# ARM.net
KiCad netlist of a schematic drawn in Altium Designer
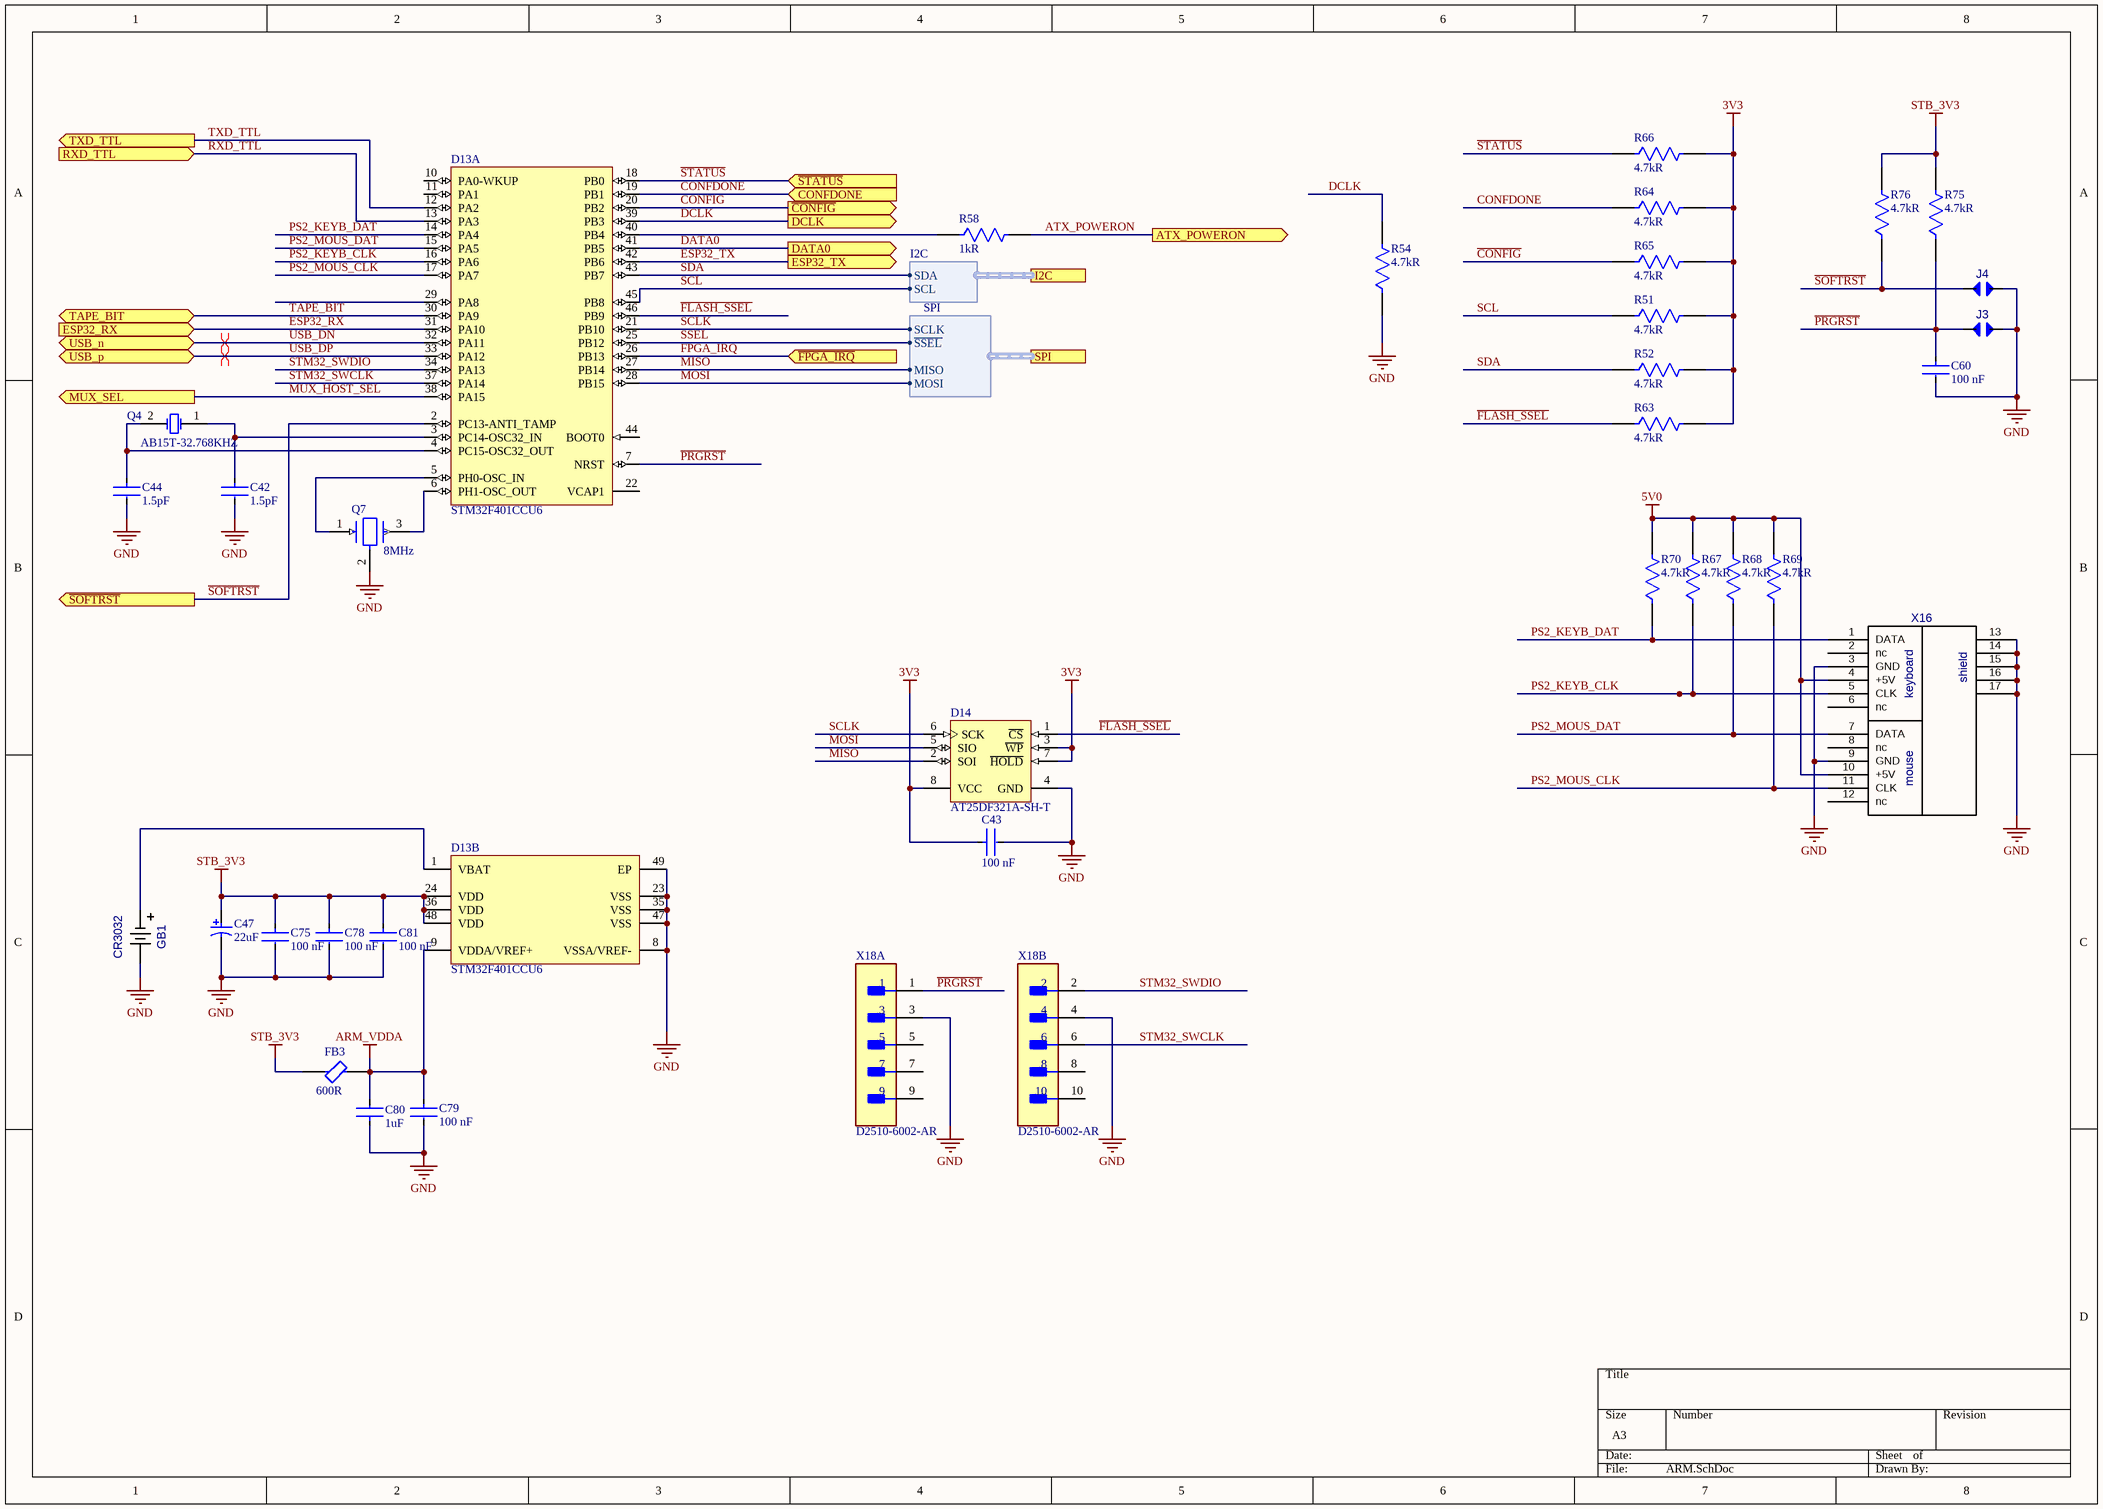
[diagram p0: ARM.SchDoc]

(export (version "E")
  (design (tool "Eeschema 10.0.6"))
  (components
    (comp (ref "C42")
      (value "CL21C1R5CBANNNC")
      (footprint "FP-CL21-IPC_A")
      (description "CL21 Series 0805 1.5pF 50V ±0.25pF Tolerance C0G Multilayer Ceramic Chip Capacitor")
      (fields (field (name "VOLTAGE") "50V") (field (name "CAPACITANCE") "1.5pF"))
      (libsource (lib "Altium Content Vault") (part "b4654b650e69147ec39a6b967a45e02"))
    )
    (comp (ref "C43")
      (value "CC0805KRX7R8BB104")
      (footprint "FP-CC0805-0_85-IPC_A")
      (description "CAP CER 0.1UF 25V X7R 0805")
      (fields
        (field (name "TOLERANCE") "0.1")
        (field (name "MANUFACTURER") "Yageo")
        (field (name "CAPACITANCE") "100 nF")
      )
      (libsource (lib "Altium Content Vault") (part "11868f565c42a9108669ba33697ecf6"))
    )
    (comp (ref "C44")
      (value "CL21C1R5CBANNNC")
      (footprint "FP-CL21-IPC_A")
      (description "CL21 Series 0805 1.5pF 50V ±0.25pF Tolerance C0G Multilayer Ceramic Chip Capacitor")
      (fields (field (name "VOLTAGE") "50V") (field (name "CAPACITANCE") "1.5pF"))
      (libsource (lib "Altium Content Vault") (part "b4654b650e69147ec39a6b967a45e02"))
    )
    (comp (ref "C47")
      (value "TAJB226K016RNJ")
      (footprint "AVX-TAJ-B-2_M")
      (description "Standard Tantalum, 22 uF, +/- 10%, 16 V, -55 to 125 degC, 2-Pin SMD (1210), RoHS, Tape and Reel")
      (fields
        (field (name "TOLERANCE") "10%")
        (field (name "CAPACITANCE") "22uF")
        (field (name "MANUFACTURER") "AVX")
      )
      (libsource (lib "Altium Content Vault") (part "CAP-P-2"))
    )
    (comp (ref "C60")
      (value "CC0805KRX7R8BB104")
      (footprint "FP-CC0805-0_85-IPC_A")
      (description "CAP CER 0.1UF 25V X7R 0805")
      (fields
        (field (name "TOLERANCE") "0.1")
        (field (name "MANUFACTURER") "Yageo")
        (field (name "CAPACITANCE") "100 nF")
      )
      (libsource (lib "Altium Content Vault") (part "11868f565c42a9108669ba33697ecf6"))
    )
    (comp (ref "C75")
      (value "CC0805KRX7R8BB104")
      (footprint "FP-CC0805-0_85-IPC_A")
      (description "CAP CER 0.1UF 25V X7R 0805")
      (fields
        (field (name "TOLERANCE") "0.1")
        (field (name "MANUFACTURER") "Yageo")
        (field (name "CAPACITANCE") "100 nF")
      )
      (libsource (lib "Altium Content Vault") (part "11868f565c42a9108669ba33697ecf6"))
    )
    (comp (ref "C78")
      (value "CC0805KRX7R8BB104")
      (footprint "FP-CC0805-0_85-IPC_A")
      (description "CAP CER 0.1UF 25V X7R 0805")
      (fields
        (field (name "TOLERANCE") "0.1")
        (field (name "MANUFACTURER") "Yageo")
        (field (name "CAPACITANCE") "100 nF")
      )
      (libsource (lib "Altium Content Vault") (part "11868f565c42a9108669ba33697ecf6"))
    )
    (comp (ref "C79")
      (value "CC0805KRX7R8BB104")
      (footprint "FP-CC0805-0_85-IPC_A")
      (description "CAP CER 0.1UF 25V X7R 0805")
      (fields
        (field (name "TOLERANCE") "0.1")
        (field (name "MANUFACTURER") "Yageo")
        (field (name "CAPACITANCE") "100 nF")
      )
      (libsource (lib "Altium Content Vault") (part "11868f565c42a9108669ba33697ecf6"))
    )
    (comp (ref "C80")
      (value "GCM21BR71E105KA56L")
      (footprint "FP-GCM21B-0_15-IPC_A")
      (description "Ceramic Capacitor for Automotive 1uF ±10% 25VDC X7R 0805 Embossed T/R")
      (fields
        (field (name "TOLERANCE") "10%")
        (field (name "VOLTAGE") "25V")
        (field (name "CAPACITANCE") "1uF")
      )
      (libsource (lib "Altium Content Vault") (part "02cd4be3c70576c341d710602a673aa"))
    )
    (comp (ref "C81")
      (value "CC0805KRX7R8BB104")
      (footprint "FP-CC0805-0_85-IPC_A")
      (description "CAP CER 0.1UF 25V X7R 0805")
      (fields
        (field (name "TOLERANCE") "0.1")
        (field (name "MANUFACTURER") "Yageo")
        (field (name "CAPACITANCE") "100 nF")
      )
      (libsource (lib "Altium Content Vault") (part "11868f565c42a9108669ba33697ecf6"))
    )
    (comp (ref "D13")
      (value "STM32F401CCU6")
      (footprint "STM-UFQFPN48_N")
      (fields (field (name "MANUFACTURER") "STMicroelectronics"))
      (libsource (lib "zxevo_c2") (part "CMP-0243-00119-2"))
    )
    (comp (ref "D14")
      (value "AT25DF321A-SH-T")
      (footprint "ADST-S2-8_N")
      (fields (field (name "MANUFACTURER") "Adesto"))
      (libsource (lib "Altium Content Vault") (part "ADST-AT25DF321A-8"))
    )
    (comp (ref "FB3")
      (value "BLM21AG601SN1J")
      (footprint "FP-BLM21-0_2-t0_85-e0_5-IPC_A")
      (description "Chip Ferrite Bead, 0805, 600Ω @ 100MHz, 0.2Ω, 25%, 700mA")
      (fields (field (name "IMPEDANCE") "600R") (field (name "TOLERANCE") "25%"))
      (libsource (lib "Altium Content Vault") (part "5f30dd21d616792df468990f7003faa"))
    )
    (comp (ref "GB1")
      (value "CR3032")
      (footprint "BAT_Primary")
      (description "BAT")
      (libsource (lib "*") (part "BAT"))
    )
    (comp (ref "J3")
      (value "JUMPER")
      (footprint "JUMPER")
      (description "Hard Reset Key")
      (libsource (lib "*") (part "JUMPER"))
    )
    (comp (ref "J4")
      (value "JUMPER")
      (footprint "JUMPER")
      (description "Soft Reset Key")
      (libsource (lib "*") (part "JUMPER"))
    )
    (comp (ref "Q4")
      (value "AB15T-32.768KHZ")
      (footprint "ABRA-AB15T-2_V")
      (fields (field (name "MANUFACTURER") "Abracon"))
      (libsource (lib "Altium Content Vault") (part "ABRA-XTAL_1-2-2"))
    )
    (comp (ref "Q7")
      (value "CSTNE8M00GH5C000R0")
      (footprint "FP-CSTNE8M00GH5C000R0-MFG")
      (description "CERAMIC RES 8.0000MHZ 33PF SMD")
      (fields (field (name "FREQUENCY") "8MHz"))
      (libsource (lib "Altium Content Vault") (part "7d37667f5012bb31280c8009ddd0b1c"))
    )
    (comp (ref "R51")
      (value "CR0805-JW-472ELF")
      (footprint "FP-CR0805-IPC_A")
      (description "Thick Film Chip Resistors 0805 4.7kΩ 0.125W 5% 200ppm/°C")
      (fields (field (name "TOLERANCE") "5%") (field (name "RESISTANCE") "4.7kR"))
      (libsource (lib "Altium Content Vault") (part "1029c3af85768c4190bb7ad29bc67b5"))
    )
    (comp (ref "R52")
      (value "CR0805-JW-472ELF")
      (footprint "FP-CR0805-IPC_A")
      (description "Thick Film Chip Resistors 0805 4.7kΩ 0.125W 5% 200ppm/°C")
      (fields (field (name "TOLERANCE") "5%") (field (name "RESISTANCE") "4.7kR"))
      (libsource (lib "Altium Content Vault") (part "1029c3af85768c4190bb7ad29bc67b5"))
    )
    (comp (ref "R54")
      (value "CR0805-JW-472ELF")
      (footprint "FP-CR0805-IPC_A")
      (description "Thick Film Chip Resistors 0805 4.7kΩ 0.125W 5% 200ppm/°C")
      (fields (field (name "TOLERANCE") "5%") (field (name "RESISTANCE") "4.7kR"))
      (libsource (lib "Altium Content Vault") (part "1029c3af85768c4190bb7ad29bc67b5"))
    )
    (comp (ref "R58")
      (value "MCR10ERTJ102")
      (footprint "FP-MCR10-IPC_A")
      (description "Thick Film Chip Resistor, 0805, 1kΩ, 5%, 200ppm/°C, 0.125W, 150V")
      (fields (field (name "RESISTANCE") "1kR") (field (name "TOLERANCE") "5%"))
      (libsource (lib "Altium Content Vault") (part "1029c3af85768c4190bb7ad29bc67b5"))
    )
    (comp (ref "R63")
      (value "CR0805-JW-472ELF")
      (footprint "FP-CR0805-IPC_A")
      (description "Thick Film Chip Resistors 0805 4.7kΩ 0.125W 5% 200ppm/°C")
      (fields (field (name "TOLERANCE") "5%") (field (name "RESISTANCE") "4.7kR"))
      (libsource (lib "Altium Content Vault") (part "1029c3af85768c4190bb7ad29bc67b5"))
    )
    (comp (ref "R64")
      (value "CR0805-JW-472ELF")
      (footprint "FP-CR0805-IPC_A")
      (description "Thick Film Chip Resistors 0805 4.7kΩ 0.125W 5% 200ppm/°C")
      (fields (field (name "TOLERANCE") "5%") (field (name "RESISTANCE") "4.7kR"))
      (libsource (lib "Altium Content Vault") (part "1029c3af85768c4190bb7ad29bc67b5"))
    )
    (comp (ref "R65")
      (value "CR0805-JW-472ELF")
      (footprint "FP-CR0805-IPC_A")
      (description "Thick Film Chip Resistors 0805 4.7kΩ 0.125W 5% 200ppm/°C")
      (fields (field (name "TOLERANCE") "5%") (field (name "RESISTANCE") "4.7kR"))
      (libsource (lib "Altium Content Vault") (part "1029c3af85768c4190bb7ad29bc67b5"))
    )
    (comp (ref "R66")
      (value "CR0805-JW-472ELF")
      (footprint "FP-CR0805-IPC_A")
      (description "Thick Film Chip Resistors 0805 4.7kΩ 0.125W 5% 200ppm/°C")
      (fields (field (name "TOLERANCE") "5%") (field (name "RESISTANCE") "4.7kR"))
      (libsource (lib "Altium Content Vault") (part "1029c3af85768c4190bb7ad29bc67b5"))
    )
    (comp (ref "R67")
      (value "CR0805-JW-472ELF")
      (footprint "FP-CR0805-IPC_A")
      (description "Thick Film Chip Resistors 0805 4.7kΩ 0.125W 5% 200ppm/°C")
      (fields (field (name "TOLERANCE") "5%") (field (name "RESISTANCE") "4.7kR"))
      (libsource (lib "Altium Content Vault") (part "1029c3af85768c4190bb7ad29bc67b5"))
    )
    (comp (ref "R68")
      (value "CR0805-JW-472ELF")
      (footprint "FP-CR0805-IPC_A")
      (description "Thick Film Chip Resistors 0805 4.7kΩ 0.125W 5% 200ppm/°C")
      (fields (field (name "TOLERANCE") "5%") (field (name "RESISTANCE") "4.7kR"))
      (libsource (lib "Altium Content Vault") (part "1029c3af85768c4190bb7ad29bc67b5"))
    )
    (comp (ref "R69")
      (value "CR0805-JW-472ELF")
      (footprint "FP-CR0805-IPC_A")
      (description "Thick Film Chip Resistors 0805 4.7kΩ 0.125W 5% 200ppm/°C")
      (fields (field (name "TOLERANCE") "5%") (field (name "RESISTANCE") "4.7kR"))
      (libsource (lib "Altium Content Vault") (part "1029c3af85768c4190bb7ad29bc67b5"))
    )
    (comp (ref "R70")
      (value "CR0805-JW-472ELF")
      (footprint "FP-CR0805-IPC_A")
      (description "Thick Film Chip Resistors 0805 4.7kΩ 0.125W 5% 200ppm/°C")
      (fields (field (name "TOLERANCE") "5%") (field (name "RESISTANCE") "4.7kR"))
      (libsource (lib "Altium Content Vault") (part "1029c3af85768c4190bb7ad29bc67b5"))
    )
    (comp (ref "R75")
      (value "CR0805-JW-472ELF")
      (footprint "FP-CR0805-IPC_A")
      (description "Thick Film Chip Resistors 0805 4.7kΩ 0.125W 5% 200ppm/°C")
      (fields (field (name "TOLERANCE") "5%") (field (name "RESISTANCE") "4.7kR"))
      (libsource (lib "Altium Content Vault") (part "1029c3af85768c4190bb7ad29bc67b5"))
    )
    (comp (ref "R76")
      (value "CR0805-JW-472ELF")
      (footprint "FP-CR0805-IPC_A")
      (description "Thick Film Chip Resistors 0805 4.7kΩ 0.125W 5% 200ppm/°C")
      (fields (field (name "TOLERANCE") "5%") (field (name "RESISTANCE") "4.7kR"))
      (libsource (lib "Altium Content Vault") (part "1029c3af85768c4190bb7ad29bc67b5"))
    )
    (comp (ref "X16") (value "KEYB-MOUSE") (footprint "MDD-6FR") (libsource (lib "*") (part "KEYB-MOUSE")))
    (comp (ref "X18")
      (value "D2510-6002-AR")
      (footprint "FP-D2510-6002-AR-MFG")
      (description "CONN HEADER VERT 10POS 2.54MM")
      (fields
        (field (name "MANUFACTURER") "3M")
        (field (name "OCTOPART") "https://octopart.com/d2510-6002-ar-3m-8399032")
      )
      (libsource (lib "Altium Content Vault") (part "e3d72e3fae012c5d23a5abbd4905472"))
    )
  )
  (nets
    (net (code "3") (name "/ATX_POWERON") (class "Default")
      (node (ref "R58") (pin "2") (pinfunction "2_2") (pintype "passive"))
    )
    (net (code "4") (name "/CONFDONE") (class "Default")
      (node (ref "D13") (pin "19") (pinfunction "PB1_19") (pintype "bidirectional"))
      (node (ref "R64") (pin "1") (pinfunction "1_1") (pintype "passive"))
    )
    (net (code "5") (name "/DATA0") (class "Default")
      (node (ref "D13") (pin "41") (pinfunction "PB5_41") (pintype "bidirectional"))
    )
    (net (code "6") (name "/DCLK") (class "Default")
      (node (ref "D13") (pin "39") (pinfunction "PB3_39") (pintype "bidirectional"))
      (node (ref "R54") (pin "2") (pinfunction "2_2") (pintype "passive"))
    )
    (net (code "7") (name "/ESP32_RX") (class "Default")
      (node (ref "D13") (pin "31") (pinfunction "PA10_31") (pintype "bidirectional"))
    )
    (net (code "8") (name "/ESP32_TX") (class "Default")
      (node (ref "D13") (pin "42") (pinfunction "PB6_42") (pintype "bidirectional"))
    )
    (net (code "9") (name "/MISO") (class "Default")
      (node (ref "D13") (pin "27") (pinfunction "PB14_27") (pintype "bidirectional"))
      (node (ref "D14") (pin "2") (pinfunction "SOI_2") (pintype "bidirectional"))
    )
    (net (code "10") (name "/MOSI") (class "Default")
      (node (ref "D13") (pin "28") (pinfunction "PB15_28") (pintype "bidirectional"))
      (node (ref "D14") (pin "5") (pinfunction "SIO_5") (pintype "bidirectional"))
    )
    (net (code "11") (name "/MUX_HOST_SEL") (class "Default")
      (node (ref "D13") (pin "38") (pinfunction "PA15_38") (pintype "bidirectional"))
    )
    (net (code "12") (name "/PS2_KEYB_CLK") (class "Default")
      (node (ref "D13") (pin "16") (pinfunction "PA6_16") (pintype "bidirectional"))
      (node (ref "R67") (pin "1") (pinfunction "1_1") (pintype "passive"))
      (node (ref "X16") (pin "5") (pinfunction "CLK_5") (pintype "passive"))
    )
    (net (code "13") (name "/PS2_KEYB_DAT") (class "Default")
      (node (ref "D13") (pin "14") (pinfunction "PA4_14") (pintype "bidirectional"))
      (node (ref "R70") (pin "1") (pinfunction "1_1") (pintype "passive"))
      (node (ref "X16") (pin "1") (pinfunction "DATA_1") (pintype "passive"))
    )
    (net (code "14") (name "/PS2_MOUS_CLK") (class "Default")
      (node (ref "D13") (pin "17") (pinfunction "PA7_17") (pintype "bidirectional"))
      (node (ref "R69") (pin "1") (pinfunction "1_1") (pintype "passive"))
      (node (ref "X16") (pin "11") (pinfunction "CLK_11") (pintype "passive"))
    )
    (net (code "15") (name "/PS2_MOUS_DAT") (class "Default")
      (node (ref "D13") (pin "15") (pinfunction "PA5_15") (pintype "bidirectional"))
      (node (ref "R68") (pin "1") (pinfunction "1_1") (pintype "passive"))
      (node (ref "X16") (pin "7") (pinfunction "DATA_7") (pintype "passive"))
    )
    (net (code "16") (name "/RXD_TTL") (class "Default")
      (node (ref "D13") (pin "13") (pinfunction "PA3_13") (pintype "bidirectional"))
    )
    (net (code "17") (name "/SCL") (class "Default")
      (node (ref "D13") (pin "45") (pinfunction "PB8_45") (pintype "bidirectional"))
      (node (ref "R51") (pin "1") (pinfunction "1_1") (pintype "passive"))
    )
    (net (code "18") (name "/SCLK") (class "Default")
      (node (ref "D13") (pin "21") (pinfunction "PB10_21") (pintype "bidirectional"))
      (node (ref "D14") (pin "6") (pinfunction "SCK_6") (pintype "input"))
    )
    (net (code "19") (name "/SDA") (class "Default")
      (node (ref "D13") (pin "43") (pinfunction "PB7_43") (pintype "bidirectional"))
      (node (ref "R52") (pin "1") (pinfunction "1_1") (pintype "passive"))
    )
    (net (code "20") (name "/STM32_SWCLK") (class "Default")
      (node (ref "D13") (pin "37") (pinfunction "PA14_37") (pintype "bidirectional"))
      (node (ref "X18") (pin "6") (pinfunction "6_6") (pintype "passive"))
    )
    (net (code "21") (name "/STM32_SWDIO") (class "Default")
      (node (ref "D13") (pin "34") (pinfunction "PA13_34") (pintype "bidirectional"))
      (node (ref "X18") (pin "2") (pinfunction "2_2") (pintype "passive"))
    )
    (net (code "22") (name "/TAPE_BIT") (class "Default")
      (node (ref "D13") (pin "30") (pinfunction "PA9_30") (pintype "bidirectional"))
    )
    (net (code "23") (name "/TXD_TTL") (class "Default")
      (node (ref "D13") (pin "12") (pinfunction "PA2_12") (pintype "bidirectional"))
    )
    (net (code "24") (name "/USB_DN") (class "Default")
      (node (ref "D13") (pin "32") (pinfunction "PA11_32") (pintype "bidirectional"))
    )
    (net (code "25") (name "/USB_DP") (class "Default")
      (node (ref "D13") (pin "33") (pinfunction "PA12_33") (pintype "bidirectional"))
    )
    (net (code "28") (name "/~{CONFIG}") (class "Default")
      (node (ref "D13") (pin "20") (pinfunction "PB2_20") (pintype "bidirectional"))
      (node (ref "R65") (pin "1") (pinfunction "1_1") (pintype "passive"))
    )
    (net (code "29") (name "/~{FLASH_SSEL}") (class "Default")
      (node (ref "D13") (pin "46") (pinfunction "PB9_46") (pintype "bidirectional"))
      (node (ref "D14") (pin "1") (pinfunction "~{CS}_1") (pintype "input"))
      (node (ref "R63") (pin "1") (pinfunction "1_1") (pintype "passive"))
    )
    (net (code "30") (name "/~{FPGA_IRQ}") (class "Default")
      (node (ref "D13") (pin "26") (pinfunction "PB13_26") (pintype "bidirectional"))
    )
    (net (code "31") (name "/~{PRGRST}") (class "Default")
      (node (ref "C60") (pin "1") (pinfunction "1_1") (pintype "passive"))
      (node (ref "D13") (pin "7") (pinfunction "NRST_7") (pintype "bidirectional"))
      (node (ref "J3") (pin "0") (pinfunction "1_0") (pintype "passive"))
      (node (ref "R75") (pin "1") (pinfunction "1_1") (pintype "passive"))
      (node (ref "X18") (pin "1") (pinfunction "1_1") (pintype "passive"))
    )
    (net (code "32") (name "/~{SOFTRST}") (class "Default")
      (node (ref "D13") (pin "2") (pinfunction "PC13-ANTI_TAMP_2") (pintype "bidirectional"))
      (node (ref "J4") (pin "0") (pinfunction "1_0") (pintype "passive"))
      (node (ref "R76") (pin "1") (pinfunction "1_1") (pintype "passive"))
    )
    (net (code "33") (name "/~{SSEL}") (class "Default")
      (node (ref "D13") (pin "25") (pinfunction "PB12_25") (pintype "bidirectional"))
    )
    (net (code "34") (name "/~{STATUS}") (class "Default")
      (node (ref "D13") (pin "18") (pinfunction "PB0_18") (pintype "bidirectional"))
      (node (ref "R66") (pin "1") (pinfunction "1_1") (pintype "passive"))
    )
    (net (code "35") (name "3V3") (class "Default")
      (node (ref "C43") (pin "1") (pinfunction "1_1") (pintype "passive"))
      (node (ref "D14") (pin "3") (pinfunction "~{WP}_3") (pintype "input"))
      (node (ref "D14") (pin "7") (pinfunction "~{HOLD}_7") (pintype "input"))
      (node (ref "D14") (pin "8") (pinfunction "VCC_8") (pintype "power_in"))
      (node (ref "R51") (pin "2") (pinfunction "2_2") (pintype "passive"))
      (node (ref "R52") (pin "2") (pinfunction "2_2") (pintype "passive"))
      (node (ref "R63") (pin "2") (pinfunction "2_2") (pintype "passive"))
      (node (ref "R64") (pin "2") (pinfunction "2_2") (pintype "passive"))
      (node (ref "R65") (pin "2") (pinfunction "2_2") (pintype "passive"))
      (node (ref "R66") (pin "2") (pinfunction "2_2") (pintype "passive"))
    )
    (net (code "36") (name "5V0") (class "Default")
      (node (ref "R67") (pin "2") (pinfunction "2_2") (pintype "passive"))
      (node (ref "R68") (pin "2") (pinfunction "2_2") (pintype "passive"))
      (node (ref "R69") (pin "2") (pinfunction "2_2") (pintype "passive"))
      (node (ref "R70") (pin "2") (pinfunction "2_2") (pintype "passive"))
      (node (ref "X16") (pin "10") (pinfunction "+5V_10") (pintype "passive"))
      (node (ref "X16") (pin "4") (pinfunction "+5V_4") (pintype "passive"))
    )
    (net (code "37") (name "ARM_VDDA") (class "Default")
      (node (ref "C79") (pin "1") (pinfunction "1_1") (pintype "passive"))
      (node (ref "C80") (pin "2") (pinfunction "2_2") (pintype "passive"))
      (node (ref "D13") (pin "9") (pinfunction "VDDA/VREF+_9") (pintype "power_in"))
      (node (ref "FB3") (pin "2") (pinfunction "2_2") (pintype "passive"))
    )
    (net (code "38") (name "GND") (class "Default")
      (node (ref "C42") (pin "2") (pinfunction "2_2") (pintype "passive"))
      (node (ref "C43") (pin "2") (pinfunction "2_2") (pintype "passive"))
      (node (ref "C44") (pin "2") (pinfunction "2_2") (pintype "passive"))
      (node (ref "C47") (pin "2") (pinfunction "2_2") (pintype "passive"))
      (node (ref "C60") (pin "2") (pinfunction "2_2") (pintype "passive"))
      (node (ref "C75") (pin "2") (pinfunction "2_2") (pintype "passive"))
      (node (ref "C78") (pin "2") (pinfunction "2_2") (pintype "passive"))
      (node (ref "C79") (pin "2") (pinfunction "2_2") (pintype "passive"))
      (node (ref "C80") (pin "1") (pinfunction "1_1") (pintype "passive"))
      (node (ref "C81") (pin "2") (pinfunction "2_2") (pintype "passive"))
      (node (ref "D13") (pin "23") (pinfunction "VSS_23") (pintype "power_in"))
      (node (ref "D13") (pin "35") (pinfunction "VSS_35") (pintype "power_in"))
      (node (ref "D13") (pin "47") (pinfunction "VSS_47") (pintype "power_in"))
      (node (ref "D13") (pin "49") (pinfunction "EP_49") (pintype "power_in"))
      (node (ref "D13") (pin "8") (pinfunction "VSSA/VREF-_8") (pintype "power_in"))
      (node (ref "D14") (pin "4") (pinfunction "GND_4") (pintype "power_in"))
      (node (ref "GB1") (pin "2") (pinfunction "MINUS_2") (pintype "passive"))
      (node (ref "J3") (pin "1") (pinfunction "2_1") (pintype "passive"))
      (node (ref "J4") (pin "1") (pinfunction "2_1") (pintype "passive"))
      (node (ref "Q7") (pin "2") (pinfunction "GND_2") (pintype "power_in"))
      (node (ref "R54") (pin "1") (pinfunction "1_1") (pintype "passive"))
      (node (ref "X16") (pin "13") (pinfunction "shield_13") (pintype "passive"))
      (node (ref "X16") (pin "14") (pinfunction "shield_14") (pintype "passive"))
      (node (ref "X16") (pin "15") (pinfunction "shield_15") (pintype "passive"))
      (node (ref "X16") (pin "16") (pinfunction "shield_16") (pintype "passive"))
      (node (ref "X16") (pin "17") (pinfunction "shield_17") (pintype "passive"))
      (node (ref "X16") (pin "3") (pinfunction "GND_3") (pintype "passive"))
      (node (ref "X16") (pin "9") (pinfunction "GND_9") (pintype "passive"))
      (node (ref "X18") (pin "3") (pinfunction "3_3") (pintype "passive"))
      (node (ref "X18") (pin "4") (pinfunction "4_4") (pintype "passive"))
    )
    (net (code "39") (name "Net-(D13A-PB4)") (class "Default")
      (node (ref "D13") (pin "40") (pinfunction "PB4_40") (pintype "bidirectional"))
      (node (ref "R58") (pin "1") (pinfunction "1_1") (pintype "passive"))
    )
    (net (code "40") (name "Net-(D13A-PC14-OSC32_IN)") (class "Default")
      (node (ref "C42") (pin "1") (pinfunction "1_1") (pintype "passive"))
      (node (ref "D13") (pin "3") (pinfunction "PC14-OSC32_IN_3") (pintype "bidirectional"))
      (node (ref "Q4") (pin "1") (pinfunction "X1_1") (pintype "passive"))
    )
    (net (code "41") (name "Net-(D13A-PC15-OSC32_OUT)") (class "Default")
      (node (ref "C44") (pin "1") (pinfunction "1_1") (pintype "passive"))
      (node (ref "D13") (pin "4") (pinfunction "PC15-OSC32_OUT_4") (pintype "bidirectional"))
      (node (ref "Q4") (pin "2") (pinfunction "X2_2") (pintype "passive"))
    )
    (net (code "42") (name "Net-(D13A-PH0-OSC_IN)") (class "Default")
      (node (ref "D13") (pin "5") (pinfunction "PH0-OSC_IN_5") (pintype "bidirectional"))
      (node (ref "Q7") (pin "1") (pinfunction "Input_1") (pintype "input"))
    )
    (net (code "43") (name "Net-(D13A-PH1-OSC_OUT)") (class "Default")
      (node (ref "D13") (pin "6") (pinfunction "PH1-OSC_OUT_6") (pintype "bidirectional"))
      (node (ref "Q7") (pin "3") (pinfunction "Output_3") (pintype "output"))
    )
    (net (code "44") (name "Net-(D13B-VBAT)") (class "Default")
      (node (ref "D13") (pin "1") (pinfunction "VBAT_1") (pintype "power_in"))
      (node (ref "GB1") (pin "1") (pinfunction "PLUS_1") (pintype "passive"))
    )
    (net (code "45") (name "STB_3V3") (class "Default")
      (node (ref "C47") (pin "1") (pinfunction "1_1") (pintype "passive"))
      (node (ref "C75") (pin "1") (pinfunction "1_1") (pintype "passive"))
      (node (ref "C78") (pin "1") (pinfunction "1_1") (pintype "passive"))
      (node (ref "C81") (pin "1") (pinfunction "1_1") (pintype "passive"))
      (node (ref "D13") (pin "24") (pinfunction "VDD_24") (pintype "power_in"))
      (node (ref "D13") (pin "36") (pinfunction "VDD_36") (pintype "power_in"))
      (node (ref "D13") (pin "48") (pinfunction "VDD_48") (pintype "power_in"))
      (node (ref "FB3") (pin "1") (pinfunction "1_1") (pintype "passive"))
      (node (ref "R75") (pin "2") (pinfunction "2_2") (pintype "passive"))
      (node (ref "R76") (pin "2") (pinfunction "2_2") (pintype "passive"))
    )
    (net (code "46") (name "unconnected-(D13A-BOOT0-Pad44)") (class "Default")
      (node (ref "D13") (pin "44") (pinfunction "BOOT0_44") (pintype "input"))
    )
    (net (code "47") (name "unconnected-(D13A-PA0-WKUP-Pad10)") (class "Default")
      (node (ref "D13") (pin "10") (pinfunction "PA0-WKUP_10") (pintype "bidirectional"))
    )
    (net (code "48") (name "unconnected-(D13A-PA1-Pad11)") (class "Default")
      (node (ref "D13") (pin "11") (pinfunction "PA1_11") (pintype "bidirectional"))
    )
    (net (code "49") (name "unconnected-(D13A-PA8-Pad29)") (class "Default")
      (node (ref "D13") (pin "29") (pinfunction "PA8_29") (pintype "bidirectional"))
    )
    (net (code "50") (name "unconnected-(D13A-VCAP1-Pad22)") (class "Default")
      (node (ref "D13") (pin "22") (pinfunction "VCAP1_22") (pintype "power_in"))
    )
    (net (code "51") (name "unconnected-(X16-nc-Pad2)") (class "Default")
      (node (ref "X16") (pin "2") (pinfunction "nc_2") (pintype "passive"))
    )
    (net (code "52") (name "unconnected-(X16-nc-Pad6)") (class "Default")
      (node (ref "X16") (pin "6") (pinfunction "nc_6") (pintype "passive"))
    )
    (net (code "53") (name "unconnected-(X16-nc-Pad8)") (class "Default")
      (node (ref "X16") (pin "8") (pinfunction "nc_8") (pintype "passive"))
    )
    (net (code "54") (name "unconnected-(X16-nc-Pad12)") (class "Default")
      (node (ref "X16") (pin "12") (pinfunction "nc_12") (pintype "passive"))
    )
    (net (code "55") (name "unconnected-(X18-Pad5)") (class "Default")
      (node (ref "X18") (pin "5") (pinfunction "5_5") (pintype "passive"))
    )
    (net (code "56") (name "unconnected-(X18-Pad7)") (class "Default")
      (node (ref "X18") (pin "7") (pinfunction "7_7") (pintype "passive"))
    )
    (net (code "57") (name "unconnected-(X18-Pad8)") (class "Default")
      (node (ref "X18") (pin "8") (pinfunction "8_8") (pintype "passive"))
    )
    (net (code "58") (name "unconnected-(X18-Pad9)") (class "Default")
      (node (ref "X18") (pin "9") (pinfunction "9_9") (pintype "passive"))
    )
    (net (code "59") (name "unconnected-(X18-Pad10)") (class "Default")
      (node (ref "X18") (pin "10") (pinfunction "10_10") (pintype "passive"))
    )
  )
)
